# nisetoro_wsc_adapter_v3.net
KiCad netlist of a schematic drawn in EAGLE
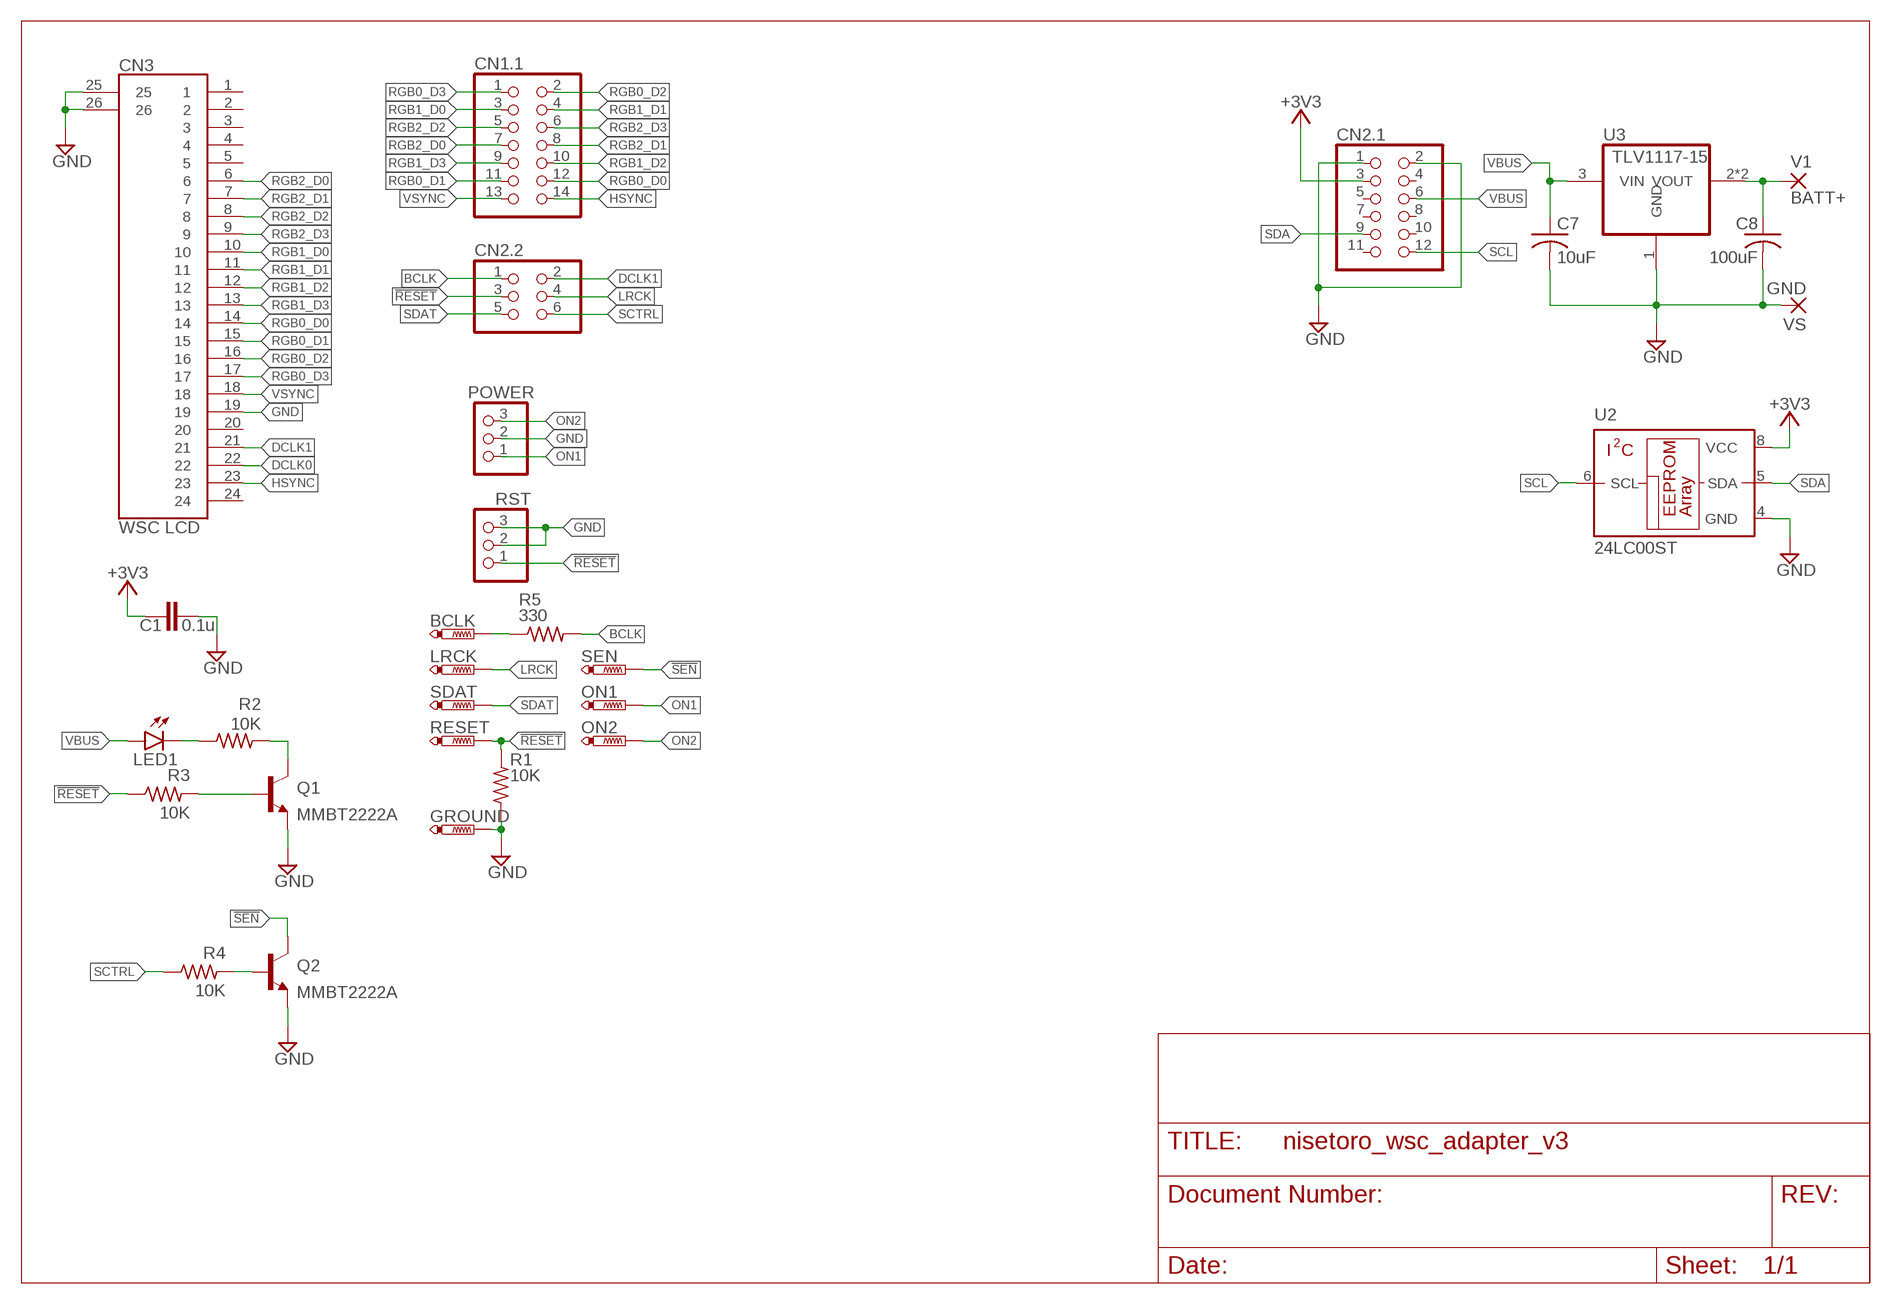
[diagram p0: schematic, sheet 1]

(export (version "E")
  (design (tool "Eeschema 10.0.6"))
  (components
    (comp (ref "BCLK")
      (value "PTR1B1,27")
      (footprint "eagle-import:B1,27")
      (libsource (lib "eagle-import") (part "PTR1B1,27"))
    )
    (comp (ref "C1")
      (value "0.1u")
      (footprint "eagle-import:C0805")
      (libsource (lib "eagle-import") (part "C-EUC0805"))
    )
    (comp (ref "C7")
      (value "10uF")
      (footprint "eagle-import:C1210")
      (libsource (lib "eagle-import") (part "C-USC1210"))
    )
    (comp (ref "C8")
      (value "100uF")
      (footprint "eagle-import:C1210")
      (libsource (lib "eagle-import") (part "C-USC1210"))
    )
    (comp (ref "CN1.1")
      (value "PINHD-2X7")
      (footprint "eagle-import:2X07")
      (libsource (lib "eagle-import") (part "PINHD-2X7"))
    )
    (comp (ref "CN2.1")
      (value "PINHD-2X6")
      (footprint "eagle-import:2X06")
      (libsource (lib "eagle-import") (part "PINHD-2X6"))
    )
    (comp (ref "CN2.2")
      (value "PINHD-2X3")
      (footprint "eagle-import:2X03")
      (libsource (lib "eagle-import") (part "PINHD-2X3"))
    )
    (comp (ref "CN3")
      (value "WSC LCD")
      (footprint "eagle-import:68712414022_R")
      (libsource (lib "eagle-import") (part "68712414022/R"))
    )
    (comp (ref "GROUND")
      (value "PTR1B1,27")
      (footprint "eagle-import:B1,27")
      (libsource (lib "eagle-import") (part "PTR1B1,27"))
    )
    (comp (ref "LED1")
      (value "LEDSML0603")
      (footprint "eagle-import:SML0603")
      (libsource (lib "eagle-import") (part "LEDSML0603"))
    )
    (comp (ref "LRCK")
      (value "PTR1B1,27")
      (footprint "eagle-import:B1,27")
      (libsource (lib "eagle-import") (part "PTR1B1,27"))
    )
    (comp (ref "ON1")
      (value "PTR1B1,27")
      (footprint "eagle-import:B1,27")
      (libsource (lib "eagle-import") (part "PTR1B1,27"))
    )
    (comp (ref "ON2")
      (value "PTR1B1,27")
      (footprint "eagle-import:B1,27")
      (libsource (lib "eagle-import") (part "PTR1B1,27"))
    )
    (comp (ref "POWER")
      (value "PINHD-1X3/ROUND")
      (footprint "eagle-import:1X03_ROUND")
      (libsource (lib "eagle-import") (part "PINHD-1X3/ROUND"))
    )
    (comp (ref "Q1")
      (value "MMBT2222A")
      (footprint "eagle-import:SOT23-BEC")
      (libsource (lib "eagle-import") (part "2N2222SOT23"))
    )
    (comp (ref "Q2")
      (value "MMBT2222A")
      (footprint "eagle-import:SOT23-BEC")
      (libsource (lib "eagle-import") (part "2N2222SOT23"))
    )
    (comp (ref "R1")
      (value "10K")
      (footprint "eagle-import:R0805")
      (libsource (lib "eagle-import") (part "R-US_R0805"))
    )
    (comp (ref "R2")
      (value "10K")
      (footprint "eagle-import:R0805")
      (libsource (lib "eagle-import") (part "R-US_R0805"))
    )
    (comp (ref "R3")
      (value "10K")
      (footprint "eagle-import:R0805")
      (libsource (lib "eagle-import") (part "R-US_R0805"))
    )
    (comp (ref "R4")
      (value "10K")
      (footprint "eagle-import:R0805")
      (libsource (lib "eagle-import") (part "R-US_R0805"))
    )
    (comp (ref "R5")
      (value "330")
      (footprint "eagle-import:R0805")
      (libsource (lib "eagle-import") (part "R-US_R0805"))
    )
    (comp (ref "RESET")
      (value "PTR1B1,27")
      (footprint "eagle-import:B1,27")
      (libsource (lib "eagle-import") (part "PTR1B1,27"))
    )
    (comp (ref "RST")
      (value "PINHD-1X3/ROUND")
      (footprint "eagle-import:1X03_ROUND")
      (libsource (lib "eagle-import") (part "PINHD-1X3/ROUND"))
    )
    (comp (ref "SDAT")
      (value "PTR1B1,27")
      (footprint "eagle-import:B1,27")
      (libsource (lib "eagle-import") (part "PTR1B1,27"))
    )
    (comp (ref "SEN")
      (value "PTR1B1,27")
      (footprint "eagle-import:B1,27")
      (libsource (lib "eagle-import") (part "PTR1B1,27"))
    )
    (comp (ref "U2")
      (value "24LC00ST")
      (footprint "eagle-import:TSSOP8")
      (fields (field (name "MF") "MICROCHIP") (field (name "MPN") "24LC00-I/ST"))
      (libsource (lib "eagle-import") (part "2400STLC"))
    )
    (comp (ref "U3")
      (value "TLV1117-15")
      (footprint "eagle-import:SOT223")
      (fields (field (name "MPN") "REG1117"))
      (libsource (lib "eagle-import") (part "REG1117"))
    )
    (comp (ref "V1")
      (value "BATT+")
      (footprint "eagle-import:SMD2,54-5,08")
      (libsource (lib "eagle-import") (part "WIREPADSMD2,54-5,08"))
    )
    (comp (ref "VS")
      (value "GND")
      (footprint "eagle-import:SMD2,54-5,08")
      (libsource (lib "eagle-import") (part "WIREPADSMD2,54-5,08"))
    )
  )
  (nets
    (net (code "1") (name "+3V3") (class "Default")
      (node (ref "C1") (pin "1") (pinfunction "1_1") (pintype "passive"))
      (node (ref "CN2.1") (pin "3") (pinfunction "3_3") (pintype "passive"))
      (node (ref "U2") (pin "8") (pinfunction "VCC_8") (pintype "power_in"))
    )
    (net (code "2") (name "/~{RESET}") (class "Default")
      (node (ref "CN2.2") (pin "3") (pinfunction "3_3") (pintype "passive"))
      (node (ref "R1") (pin "2") (pinfunction "2_2") (pintype "passive"))
      (node (ref "R3") (pin "1") (pinfunction "1_1") (pintype "passive"))
      (node (ref "RESET") (pin "TP") (pinfunction "TP_TP") (pintype "input"))
      (node (ref "RST") (pin "1") (pinfunction "1_1") (pintype "passive"))
    )
    (net (code "3") (name "/~{SEN}") (class "Default")
      (node (ref "Q2") (pin "C") (pinfunction "C_C") (pintype "passive"))
      (node (ref "SEN") (pin "TP") (pinfunction "TP_TP") (pintype "input"))
    )
    (net (code "4") (name "BCLK") (class "Default")
      (node (ref "CN2.2") (pin "1") (pinfunction "1_1") (pintype "passive"))
      (node (ref "R5") (pin "2") (pinfunction "2_2") (pintype "passive"))
    )
    (net (code "5") (name "DCLK0") (class "Default")
      (node (ref "CN3") (pin "22") (pinfunction "22_22") (pintype "bidirectional"))
    )
    (net (code "6") (name "DCLK1") (class "Default")
      (node (ref "CN2.2") (pin "2") (pinfunction "2_2") (pintype "passive"))
      (node (ref "CN3") (pin "21") (pinfunction "21_21") (pintype "bidirectional"))
    )
    (net (code "7") (name "GND") (class "Default")
      (node (ref "C1") (pin "2") (pinfunction "2_2") (pintype "passive"))
      (node (ref "C7") (pin "2") (pinfunction "2_2") (pintype "passive"))
      (node (ref "C8") (pin "2") (pinfunction "2_2") (pintype "passive"))
      (node (ref "CN2.1") (pin "1") (pinfunction "1_1") (pintype "passive"))
      (node (ref "CN2.1") (pin "2") (pinfunction "2_2") (pintype "passive"))
      (node (ref "CN3") (pin "19") (pinfunction "19_19") (pintype "bidirectional"))
      (node (ref "CN3") (pin "25") (pinfunction "25_25") (pintype "bidirectional"))
      (node (ref "CN3") (pin "26") (pinfunction "26_26") (pintype "bidirectional"))
      (node (ref "GROUND") (pin "TP") (pinfunction "TP_TP") (pintype "input"))
      (node (ref "POWER") (pin "2") (pinfunction "2_2") (pintype "passive"))
      (node (ref "Q1") (pin "E") (pinfunction "E_E") (pintype "passive"))
      (node (ref "Q2") (pin "E") (pinfunction "E_E") (pintype "passive"))
      (node (ref "R1") (pin "1") (pinfunction "1_1") (pintype "passive"))
      (node (ref "RST") (pin "2") (pinfunction "2_2") (pintype "passive"))
      (node (ref "RST") (pin "3") (pinfunction "3_3") (pintype "passive"))
      (node (ref "U2") (pin "4") (pinfunction "GND_4") (pintype "power_in"))
      (node (ref "U3") (pin "1") (pinfunction "GND_1") (pintype "power_in"))
      (node (ref "VS") (pin "1") (pinfunction "P_1") (pintype "passive"))
    )
    (net (code "8") (name "HSYNC") (class "Default")
      (node (ref "CN1.1") (pin "14") (pinfunction "14_14") (pintype "passive"))
      (node (ref "CN3") (pin "23") (pinfunction "23_23") (pintype "bidirectional"))
    )
    (net (code "9") (name "LRCK") (class "Default")
      (node (ref "CN2.2") (pin "4") (pinfunction "4_4") (pintype "passive"))
      (node (ref "LRCK") (pin "TP") (pinfunction "TP_TP") (pintype "input"))
    )
    (net (code "10") (name "Net-(BCLK-PadTP)") (class "Default")
      (node (ref "BCLK") (pin "TP") (pinfunction "TP_TP") (pintype "input"))
      (node (ref "R5") (pin "1") (pinfunction "1_1") (pintype "passive"))
    )
    (net (code "11") (name "Net-(LED1-PadC)") (class "Default")
      (node (ref "LED1") (pin "C") (pinfunction "C_C") (pintype "passive"))
      (node (ref "R2") (pin "1") (pinfunction "1_1") (pintype "passive"))
    )
    (net (code "12") (name "Net-(Q1-PadB)") (class "Default")
      (node (ref "Q1") (pin "B") (pinfunction "B_B") (pintype "passive"))
      (node (ref "R3") (pin "2") (pinfunction "2_2") (pintype "passive"))
    )
    (net (code "13") (name "Net-(Q1-PadC)") (class "Default")
      (node (ref "Q1") (pin "C") (pinfunction "C_C") (pintype "passive"))
      (node (ref "R2") (pin "2") (pinfunction "2_2") (pintype "passive"))
    )
    (net (code "14") (name "Net-(Q2-PadB)") (class "Default")
      (node (ref "Q2") (pin "B") (pinfunction "B_B") (pintype "passive"))
      (node (ref "R4") (pin "2") (pinfunction "2_2") (pintype "passive"))
    )
    (net (code "15") (name "Net-(V1-P)") (class "Default")
      (node (ref "C8") (pin "1") (pinfunction "1_1") (pintype "passive"))
      (node (ref "U3") (pin "2") (pinfunction "VOUT_2") (pintype "output"))
      (node (ref "U3") (pin "4") (pinfunction "VOUT_4") (pintype "output"))
      (node (ref "V1") (pin "1") (pinfunction "P_1") (pintype "passive"))
    )
    (net (code "16") (name "ON1") (class "Default")
      (node (ref "ON1") (pin "TP") (pinfunction "TP_TP") (pintype "input"))
      (node (ref "POWER") (pin "1") (pinfunction "1_1") (pintype "passive"))
    )
    (net (code "17") (name "ON2") (class "Default")
      (node (ref "ON2") (pin "TP") (pinfunction "TP_TP") (pintype "input"))
      (node (ref "POWER") (pin "3") (pinfunction "3_3") (pintype "passive"))
    )
    (net (code "18") (name "RGB0_D0") (class "Default")
      (node (ref "CN1.1") (pin "12") (pinfunction "12_12") (pintype "passive"))
      (node (ref "CN3") (pin "14") (pinfunction "14_14") (pintype "bidirectional"))
    )
    (net (code "19") (name "RGB0_D1") (class "Default")
      (node (ref "CN1.1") (pin "11") (pinfunction "11_11") (pintype "passive"))
      (node (ref "CN3") (pin "15") (pinfunction "15_15") (pintype "bidirectional"))
    )
    (net (code "20") (name "RGB0_D2") (class "Default")
      (node (ref "CN1.1") (pin "2") (pinfunction "2_2") (pintype "passive"))
      (node (ref "CN3") (pin "16") (pinfunction "16_16") (pintype "bidirectional"))
    )
    (net (code "21") (name "RGB0_D3") (class "Default")
      (node (ref "CN1.1") (pin "1") (pinfunction "1_1") (pintype "passive"))
      (node (ref "CN3") (pin "17") (pinfunction "17_17") (pintype "bidirectional"))
    )
    (net (code "22") (name "RGB1_D0") (class "Default")
      (node (ref "CN1.1") (pin "3") (pinfunction "3_3") (pintype "passive"))
      (node (ref "CN3") (pin "10") (pinfunction "10_10") (pintype "bidirectional"))
    )
    (net (code "23") (name "RGB1_D1") (class "Default")
      (node (ref "CN1.1") (pin "4") (pinfunction "4_4") (pintype "passive"))
      (node (ref "CN3") (pin "11") (pinfunction "11_11") (pintype "bidirectional"))
    )
    (net (code "24") (name "RGB1_D2") (class "Default")
      (node (ref "CN1.1") (pin "10") (pinfunction "10_10") (pintype "passive"))
      (node (ref "CN3") (pin "12") (pinfunction "12_12") (pintype "bidirectional"))
    )
    (net (code "25") (name "RGB1_D3") (class "Default")
      (node (ref "CN1.1") (pin "9") (pinfunction "9_9") (pintype "passive"))
      (node (ref "CN3") (pin "13") (pinfunction "13_13") (pintype "bidirectional"))
    )
    (net (code "26") (name "RGB2_D0") (class "Default")
      (node (ref "CN1.1") (pin "7") (pinfunction "7_7") (pintype "passive"))
      (node (ref "CN3") (pin "6") (pinfunction "6_6") (pintype "bidirectional"))
    )
    (net (code "27") (name "RGB2_D1") (class "Default")
      (node (ref "CN1.1") (pin "8") (pinfunction "8_8") (pintype "passive"))
      (node (ref "CN3") (pin "7") (pinfunction "7_7") (pintype "bidirectional"))
    )
    (net (code "28") (name "RGB2_D2") (class "Default")
      (node (ref "CN1.1") (pin "5") (pinfunction "5_5") (pintype "passive"))
      (node (ref "CN3") (pin "8") (pinfunction "8_8") (pintype "bidirectional"))
    )
    (net (code "29") (name "RGB2_D3") (class "Default")
      (node (ref "CN1.1") (pin "6") (pinfunction "6_6") (pintype "passive"))
      (node (ref "CN3") (pin "9") (pinfunction "9_9") (pintype "bidirectional"))
    )
    (net (code "30") (name "SCL") (class "Default")
      (node (ref "CN2.1") (pin "12") (pinfunction "12_12") (pintype "passive"))
      (node (ref "U2") (pin "6") (pinfunction "SCL_6") (pintype "input"))
    )
    (net (code "31") (name "SCTRL") (class "Default")
      (node (ref "CN2.2") (pin "6") (pinfunction "6_6") (pintype "passive"))
      (node (ref "R4") (pin "1") (pinfunction "1_1") (pintype "passive"))
    )
    (net (code "32") (name "SDA") (class "Default")
      (node (ref "CN2.1") (pin "9") (pinfunction "9_9") (pintype "passive"))
      (node (ref "U2") (pin "5") (pinfunction "SDA_5") (pintype "bidirectional"))
    )
    (net (code "33") (name "SDAT") (class "Default")
      (node (ref "CN2.2") (pin "5") (pinfunction "5_5") (pintype "passive"))
      (node (ref "SDAT") (pin "TP") (pinfunction "TP_TP") (pintype "input"))
    )
    (net (code "34") (name "VBUS") (class "Default")
      (node (ref "C7") (pin "1") (pinfunction "1_1") (pintype "passive"))
      (node (ref "CN2.1") (pin "6") (pinfunction "6_6") (pintype "passive"))
      (node (ref "LED1") (pin "A") (pinfunction "A_A") (pintype "passive"))
      (node (ref "U3") (pin "3") (pinfunction "VIN_3") (pintype "input"))
    )
    (net (code "35") (name "VSYNC") (class "Default")
      (node (ref "CN1.1") (pin "13") (pinfunction "13_13") (pintype "passive"))
      (node (ref "CN3") (pin "18") (pinfunction "18_18") (pintype "bidirectional"))
    )
    (net (code "36") (name "unconnected-(CN2.1-Pad4)") (class "Default")
      (node (ref "CN2.1") (pin "4") (pinfunction "4_4") (pintype "passive"))
    )
    (net (code "37") (name "unconnected-(CN2.1-Pad5)") (class "Default")
      (node (ref "CN2.1") (pin "5") (pinfunction "5_5") (pintype "passive"))
    )
    (net (code "38") (name "unconnected-(CN2.1-Pad7)") (class "Default")
      (node (ref "CN2.1") (pin "7") (pinfunction "7_7") (pintype "passive"))
    )
    (net (code "39") (name "unconnected-(CN2.1-Pad8)") (class "Default")
      (node (ref "CN2.1") (pin "8") (pinfunction "8_8") (pintype "passive"))
    )
    (net (code "40") (name "unconnected-(CN2.1-Pad10)") (class "Default")
      (node (ref "CN2.1") (pin "10") (pinfunction "10_10") (pintype "passive"))
    )
    (net (code "41") (name "unconnected-(CN2.1-Pad11)") (class "Default")
      (node (ref "CN2.1") (pin "11") (pinfunction "11_11") (pintype "passive"))
    )
    (net (code "42") (name "unconnected-(CN3-Pad1)") (class "Default")
      (node (ref "CN3") (pin "1") (pinfunction "1_1") (pintype "bidirectional"))
    )
    (net (code "43") (name "unconnected-(CN3-Pad2)") (class "Default")
      (node (ref "CN3") (pin "2") (pinfunction "2_2") (pintype "bidirectional"))
    )
    (net (code "44") (name "unconnected-(CN3-Pad3)") (class "Default")
      (node (ref "CN3") (pin "3") (pinfunction "3_3") (pintype "bidirectional"))
    )
    (net (code "45") (name "unconnected-(CN3-Pad4)") (class "Default")
      (node (ref "CN3") (pin "4") (pinfunction "4_4") (pintype "bidirectional"))
    )
    (net (code "46") (name "unconnected-(CN3-Pad5)") (class "Default")
      (node (ref "CN3") (pin "5") (pinfunction "5_5") (pintype "bidirectional"))
    )
    (net (code "47") (name "unconnected-(CN3-Pad20)") (class "Default")
      (node (ref "CN3") (pin "20") (pinfunction "20_20") (pintype "bidirectional"))
    )
    (net (code "48") (name "unconnected-(CN3-Pad24)") (class "Default")
      (node (ref "CN3") (pin "24") (pinfunction "24_24") (pintype "bidirectional"))
    )
  )
)
